# Bio_v4_LCD0_2.net
KiCad netlist of a schematic drawn in EAGLE
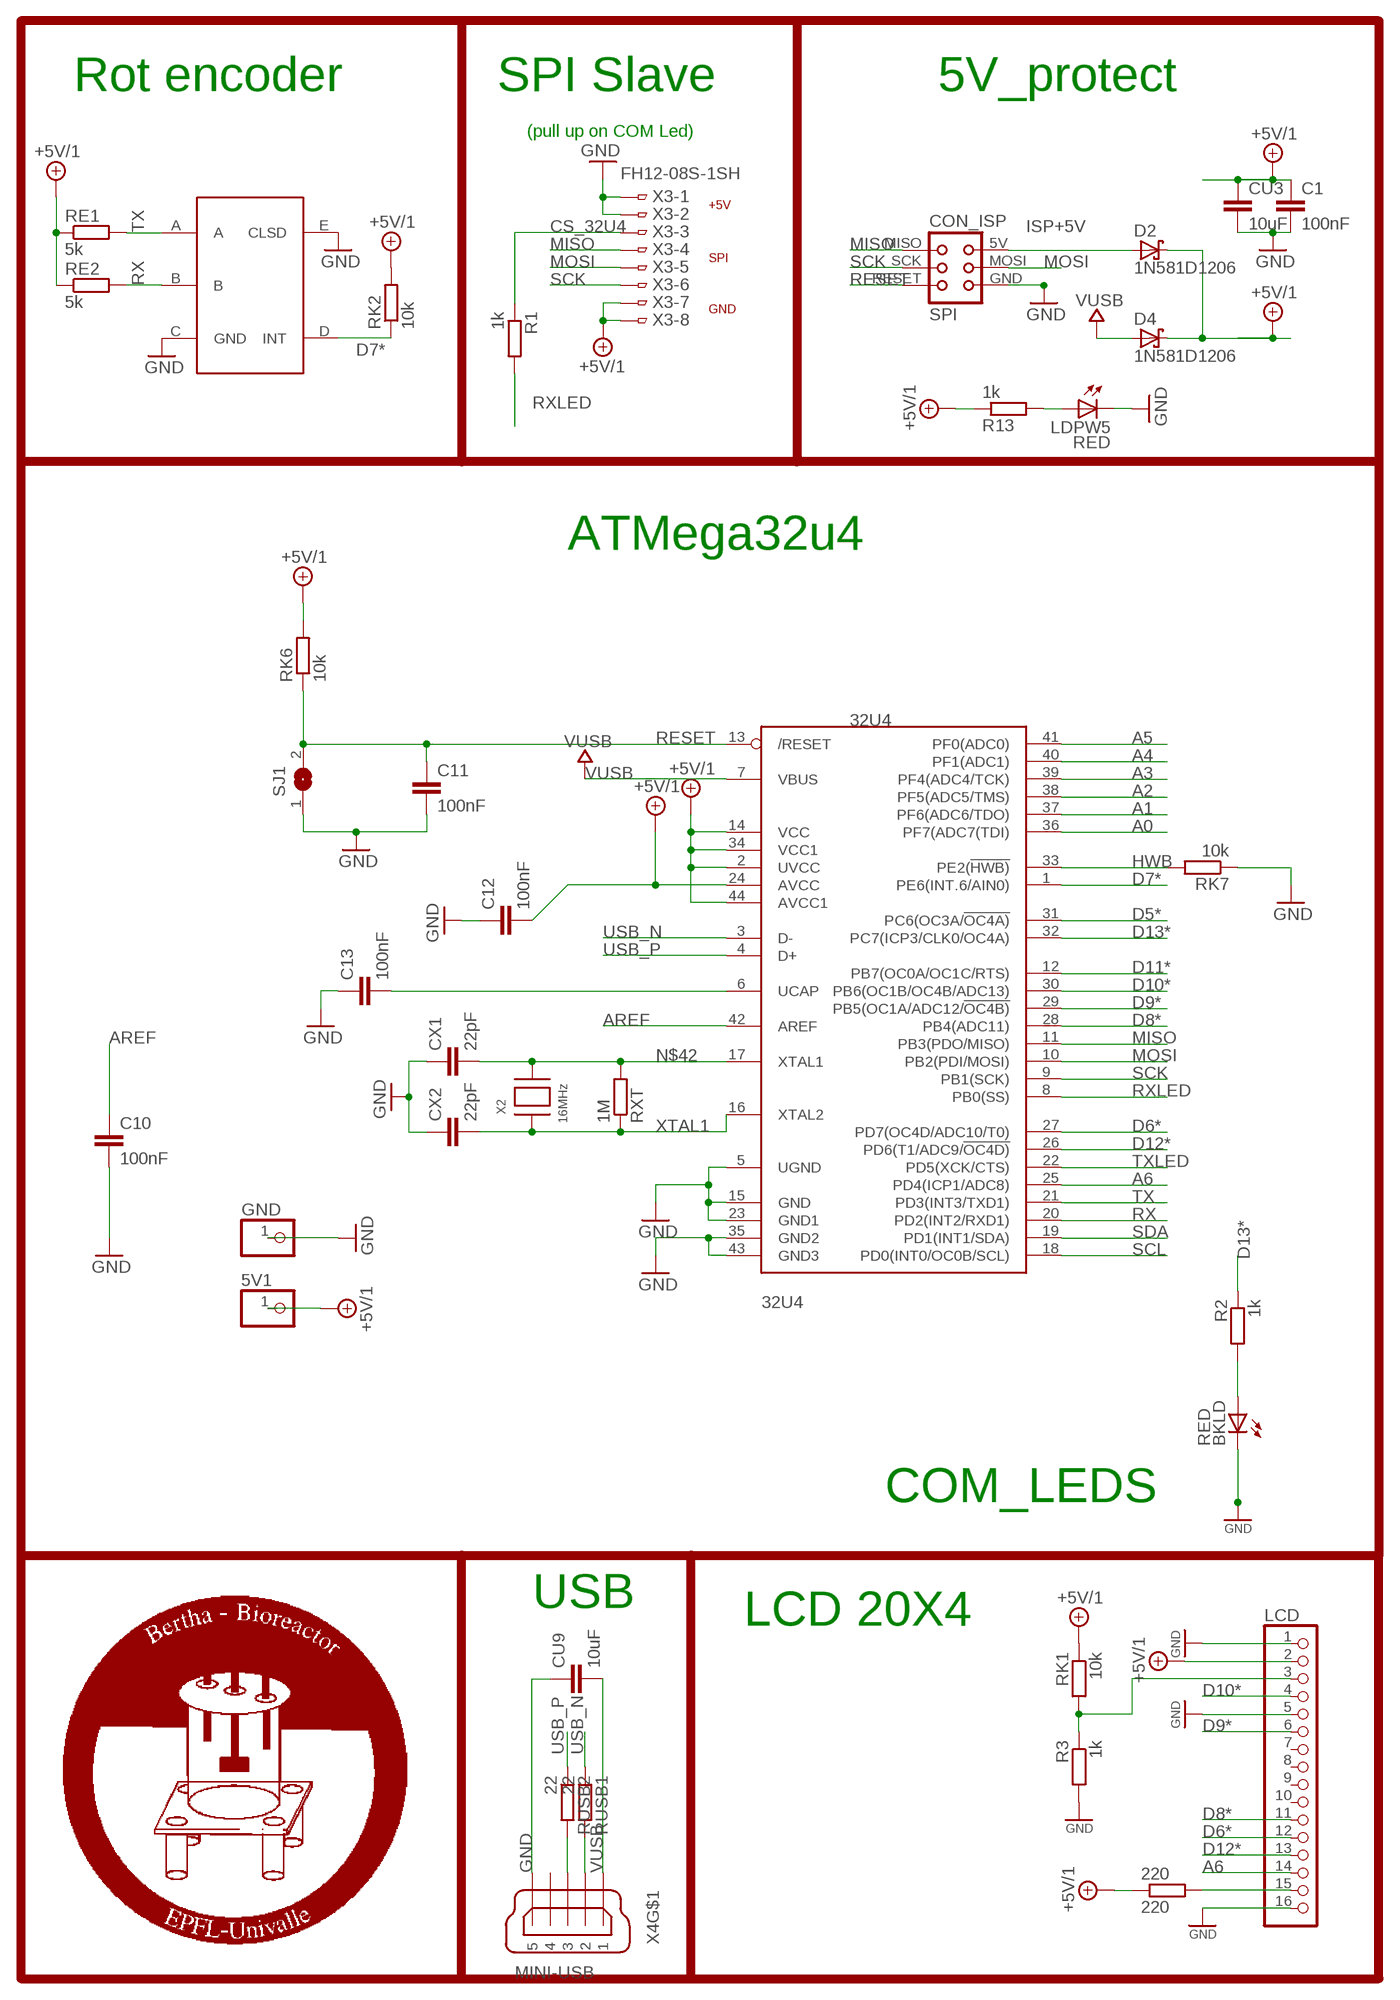
[diagram p0: schematic, sheet 1]

(export (version "E")
  (design (tool "Eeschema 10.0.6"))
  (components
    (comp (ref "5V1")
      (value "PINHD-1X1")
      (footprint "eagle-import:1X01")
      (libsource (lib "eagle-import") (part "PINHD-1X1"))
    )
    (comp (ref "32U4")
      (value "32U4")
      (footprint "eagle-import:TQFP44")
      (libsource (lib "eagle-import") (part "ATMEGA32U4-AU"))
    )
    (comp (ref "220")
      (value "220")
      (footprint "eagle-import:R0805")
      (libsource (lib "eagle-import") (part "R-EU_R0805"))
    )
    (comp (ref "BKLD")
      (value "RED")
      (footprint "eagle-import:CHIP-LED0805")
      (libsource (lib "eagle-import") (part "LEDCHIP-LED0805"))
    )
    (comp (ref "C1")
      (value "100nF")
      (footprint "eagle-import:C1206")
      (libsource (lib "eagle-import") (part "C-EUC1206"))
    )
    (comp (ref "C10")
      (value "100nF")
      (footprint "eagle-import:C1206")
      (libsource (lib "eagle-import") (part "C-EUC1206"))
    )
    (comp (ref "C11")
      (value "100nF")
      (footprint "eagle-import:C1206")
      (libsource (lib "eagle-import") (part "C-EUC1206"))
    )
    (comp (ref "C12")
      (value "100nF")
      (footprint "eagle-import:C1206")
      (libsource (lib "eagle-import") (part "C-EUC1206"))
    )
    (comp (ref "C13")
      (value "100nF")
      (footprint "eagle-import:C1206")
      (libsource (lib "eagle-import") (part "C-EUC1206"))
    )
    (comp (ref "CON_ISP")
      (value "SPI")
      (footprint "eagle-import:TC2030-MCP-NL")
      (libsource (lib "eagle-import") (part "TINYISPT"))
    )
    (comp (ref "CU3")
      (value "10uF")
      (footprint "eagle-import:C1206")
      (libsource (lib "eagle-import") (part "C-EUC1206"))
    )
    (comp (ref "CU9")
      (value "10uF")
      (footprint "eagle-import:C1206")
      (libsource (lib "eagle-import") (part "C-EUC1206"))
    )
    (comp (ref "CX1")
      (value "22pF")
      (footprint "eagle-import:C1206")
      (libsource (lib "eagle-import") (part "C-EUC1206"))
    )
    (comp (ref "CX2")
      (value "22pF")
      (footprint "eagle-import:C1206")
      (libsource (lib "eagle-import") (part "C-EUC1206"))
    )
    (comp (ref "D2")
      (value "1N581D1206")
      (footprint "eagle-import:LED-1206")
      (libsource (lib "eagle-import") (part "1N581D1206"))
    )
    (comp (ref "D4")
      (value "1N581D1206")
      (footprint "eagle-import:LED-1206")
      (libsource (lib "eagle-import") (part "1N581D1206"))
    )
    (comp (ref "GND")
      (value "PINHD-1X1")
      (footprint "eagle-import:1X01")
      (libsource (lib "eagle-import") (part "PINHD-1X1"))
    )
    (comp (ref "LCD")
      (value "LCD-HEADER")
      (footprint "eagle-import:1X16")
      (libsource (lib "eagle-import") (part "LCD-HEADER"))
    )
    (comp (ref "LDPW5")
      (value "RED")
      (footprint "eagle-import:CHIP-LED0805")
      (libsource (lib "eagle-import") (part "LEDCHIP-LED0805"))
    )
    (comp (ref "R1")
      (value "1k")
      (footprint "eagle-import:R0805")
      (libsource (lib "eagle-import") (part "R-EU_R0805"))
    )
    (comp (ref "R2")
      (value "1k")
      (footprint "eagle-import:R0805")
      (libsource (lib "eagle-import") (part "R-EU_R0805"))
    )
    (comp (ref "R3")
      (value "1k")
      (footprint "eagle-import:R0805")
      (libsource (lib "eagle-import") (part "R-EU_R0805"))
    )
    (comp (ref "R13")
      (value "1k")
      (footprint "eagle-import:R0805")
      (libsource (lib "eagle-import") (part "resistor_R-EU_R0805"))
    )
    (comp (ref "RE1")
      (value "5k")
      (footprint "eagle-import:R0805")
      (libsource (lib "eagle-import") (part "R-EU_R0805"))
    )
    (comp (ref "RE2")
      (value "5k")
      (footprint "eagle-import:R0805")
      (libsource (lib "eagle-import") (part "R-EU_R0805"))
    )
    (comp (ref "RK1")
      (value "10k")
      (footprint "eagle-import:R0805")
      (libsource (lib "eagle-import") (part "R-EU_R0805"))
    )
    (comp (ref "RK2")
      (value "10k")
      (footprint "eagle-import:M0805")
      (libsource (lib "eagle-import") (part "resistor_R-EU_M0805"))
    )
    (comp (ref "RK6")
      (value "10k")
      (footprint "eagle-import:M0805")
      (libsource (lib "eagle-import") (part "resistor_R-EU_M0805"))
    )
    (comp (ref "RK7")
      (value "10k")
      (footprint "eagle-import:M0805")
      (libsource (lib "eagle-import") (part "resistor_R-EU_M0805"))
    )
    (comp (ref "RUSB1")
      (value "22")
      (footprint "eagle-import:M1206")
      (libsource (lib "eagle-import") (part "resistor_R-EU_M1206"))
    )
    (comp (ref "RUSB2")
      (value "22")
      (footprint "eagle-import:M1206")
      (libsource (lib "eagle-import") (part "resistor_R-EU_M1206"))
    )
    (comp (ref "RXT")
      (value "1M")
      (footprint "eagle-import:R0805")
      (libsource (lib "eagle-import") (part "R-EU_R0805"))
    )
    (comp (ref "SJ1") (value "SJ") (footprint "eagle-import:SJ") (libsource (lib "eagle-import") (part "SJ")))
    (comp (ref "U$1")
      (value "EC11E")
      (footprint "eagle-import:EC11E")
      (libsource (lib "eagle-import") (part "EC11E"))
    )
    (comp (ref "X2")
      (value "16MHz")
      (footprint "eagle-import:NX6035")
      (libsource (lib "eagle-import") (part "XTALNX6035"))
    )
    (comp (ref "X3")
      (value "FH12-08S-1SH")
      (footprint "eagle-import:FH12-08S-1SH")
      (libsource (lib "eagle-import") (part "FH12-08S-1SH"))
    )
    (comp (ref "X4")
      (value "MINI-USB")
      (footprint "eagle-import:32005-201")
      (libsource (lib "eagle-import") (part "MINI-USB-SCHIELD-32005-201"))
    )
  )
  (nets
    (net (code "1") (name "+5V{slash}1") (class "Default")
      (node (ref "220") (pin "1") (pinfunction "1_1") (pintype "passive"))
      (node (ref "32U4") (pin "14") (pinfunction "VCC_14") (pintype "bidirectional"))
      (node (ref "32U4") (pin "2") (pinfunction "UVCC_2") (pintype "bidirectional"))
      (node (ref "32U4") (pin "24") (pinfunction "AVCC_24") (pintype "bidirectional"))
      (node (ref "32U4") (pin "34") (pinfunction "VCC1_34") (pintype "bidirectional"))
      (node (ref "32U4") (pin "44") (pinfunction "AVCC1_44") (pintype "bidirectional"))
      (node (ref "5V1") (pin "1") (pinfunction "1_1") (pintype "passive"))
      (node (ref "C1") (pin "1") (pinfunction "1_1") (pintype "passive"))
      (node (ref "C12") (pin "2") (pinfunction "2_2") (pintype "passive"))
      (node (ref "CU3") (pin "1") (pinfunction "1_1") (pintype "passive"))
      (node (ref "D2") (pin "C") (pinfunction "C_C") (pintype "passive"))
      (node (ref "D4") (pin "C") (pinfunction "C_C") (pintype "passive"))
      (node (ref "LCD") (pin "2") (pinfunction "2_2") (pintype "passive"))
      (node (ref "R13") (pin "1") (pinfunction "1_1") (pintype "passive"))
      (node (ref "RE1") (pin "1") (pinfunction "1_1") (pintype "passive"))
      (node (ref "RE2") (pin "1") (pinfunction "1_1") (pintype "passive"))
      (node (ref "RK1") (pin "1") (pinfunction "1_1") (pintype "passive"))
      (node (ref "RK2") (pin "2") (pinfunction "2_2") (pintype "passive"))
      (node (ref "RK6") (pin "2") (pinfunction "2_2") (pintype "passive"))
      (node (ref "X3") (pin "7") (pinfunction "1_7") (pintype "passive"))
      (node (ref "X3") (pin "8") (pinfunction "1_8") (pintype "passive"))
    )
    (net (code "2") (name "/A0") (class "Default")
      (node (ref "32U4") (pin "36") (pinfunction "PF7(ADC7(TDI)_36") (pintype "bidirectional"))
    )
    (net (code "3") (name "/A1") (class "Default")
      (node (ref "32U4") (pin "37") (pinfunction "PF6(ADC6/TDO)_37") (pintype "bidirectional"))
    )
    (net (code "4") (name "/A2") (class "Default")
      (node (ref "32U4") (pin "38") (pinfunction "PF5(ADC5/TMS)_38") (pintype "bidirectional"))
    )
    (net (code "5") (name "/A3") (class "Default")
      (node (ref "32U4") (pin "39") (pinfunction "PF4(ADC4/TCK)_39") (pintype "bidirectional"))
    )
    (net (code "6") (name "/A4") (class "Default")
      (node (ref "32U4") (pin "40") (pinfunction "PF1(ADC1)_40") (pintype "bidirectional"))
    )
    (net (code "7") (name "/A5") (class "Default")
      (node (ref "32U4") (pin "41") (pinfunction "PF0(ADC0)_41") (pintype "bidirectional"))
    )
    (net (code "8") (name "/A6") (class "Default")
      (node (ref "32U4") (pin "25") (pinfunction "PD4(ICP1/ADC8)_25") (pintype "bidirectional"))
      (node (ref "LCD") (pin "14") (pinfunction "14_14") (pintype "passive"))
    )
    (net (code "9") (name "/AREF") (class "Default")
      (node (ref "32U4") (pin "42") (pinfunction "AREF_42") (pintype "bidirectional"))
      (node (ref "C10") (pin "1") (pinfunction "1_1") (pintype "passive"))
    )
    (net (code "10") (name "/CS_32U4") (class "Default")
      (node (ref "R1") (pin "1") (pinfunction "1_1") (pintype "passive"))
      (node (ref "X3") (pin "3") (pinfunction "1_3") (pintype "passive"))
    )
    (net (code "11") (name "/D5*") (class "Default")
      (node (ref "32U4") (pin "31") (pinfunction "PC6(OC3A/~{OC4A})_31") (pintype "bidirectional"))
    )
    (net (code "12") (name "/D6*") (class "Default")
      (node (ref "32U4") (pin "27") (pinfunction "PD7(OC4D/ADC10/T0)_27") (pintype "bidirectional"))
      (node (ref "LCD") (pin "12") (pinfunction "12_12") (pintype "passive"))
    )
    (net (code "13") (name "/D7*") (class "Default")
      (node (ref "32U4") (pin "1") (pinfunction "PE6(INT.6/AIN0)_1") (pintype "bidirectional"))
      (node (ref "RK2") (pin "1") (pinfunction "1_1") (pintype "passive"))
      (node (ref "U$1") (pin "D") (pinfunction "INT_D") (pintype "bidirectional"))
    )
    (net (code "14") (name "/D8*") (class "Default")
      (node (ref "32U4") (pin "28") (pinfunction "PB4(ADC11)_28") (pintype "bidirectional"))
      (node (ref "LCD") (pin "11") (pinfunction "11_11") (pintype "passive"))
    )
    (net (code "15") (name "/D9*") (class "Default")
      (node (ref "32U4") (pin "29") (pinfunction "PB5(OC1A/ADC12/~{OC4B})_29") (pintype "bidirectional"))
      (node (ref "LCD") (pin "6") (pinfunction "6_6") (pintype "passive"))
    )
    (net (code "16") (name "/D10*") (class "Default")
      (node (ref "32U4") (pin "30") (pinfunction "PB6(OC1B/OC4B/ADC13)_30") (pintype "bidirectional"))
      (node (ref "LCD") (pin "4") (pinfunction "4_4") (pintype "passive"))
    )
    (net (code "17") (name "/D11*") (class "Default")
      (node (ref "32U4") (pin "12") (pinfunction "PB7(OC0A/OC1C/RTS)_12") (pintype "bidirectional"))
    )
    (net (code "18") (name "/D12*") (class "Default")
      (node (ref "32U4") (pin "26") (pinfunction "PD6(T1/ADC9/~{OC4D})_26") (pintype "bidirectional"))
      (node (ref "LCD") (pin "13") (pinfunction "13_13") (pintype "passive"))
    )
    (net (code "19") (name "/D13*") (class "Default")
      (node (ref "32U4") (pin "32") (pinfunction "PC7(ICP3/CLK0/OC4A)_32") (pintype "bidirectional"))
      (node (ref "R2") (pin "1") (pinfunction "1_1") (pintype "passive"))
    )
    (net (code "20") (name "/HWB") (class "Default")
      (node (ref "32U4") (pin "33") (pinfunction "PE2(~{HWB})_33") (pintype "bidirectional"))
      (node (ref "RK7") (pin "2") (pinfunction "2_2") (pintype "passive"))
    )
    (net (code "21") (name "/ISP+5V") (class "Default")
      (node (ref "CON_ISP") (pin "5V") (pinfunction "VCC_5V") (pintype "passive"))
      (node (ref "D2") (pin "A") (pinfunction "A_A") (pintype "passive"))
    )
    (net (code "22") (name "/MISO") (class "Default")
      (node (ref "32U4") (pin "11") (pinfunction "PB3(PDO/MISO)_11") (pintype "bidirectional"))
      (node (ref "CON_ISP") (pin "MISO") (pinfunction "MISO_MISO") (pintype "passive"))
      (node (ref "X3") (pin "4") (pinfunction "1_4") (pintype "passive"))
    )
    (net (code "23") (name "/MOSI") (class "Default")
      (node (ref "32U4") (pin "10") (pinfunction "PB2(PDI/MOSI)_10") (pintype "bidirectional"))
      (node (ref "CON_ISP") (pin "MOSI") (pinfunction "MOSI_MOSI") (pintype "passive"))
      (node (ref "X3") (pin "5") (pinfunction "1_5") (pintype "passive"))
    )
    (net (code "24") (name "/N$42") (class "Default")
      (node (ref "32U4") (pin "17") (pinfunction "XTAL1_17") (pintype "bidirectional"))
      (node (ref "CX1") (pin "2") (pinfunction "2_2") (pintype "passive"))
      (node (ref "RXT") (pin "2") (pinfunction "2_2") (pintype "passive"))
      (node (ref "X2") (pin "P$2") (pinfunction "P$2_P$2") (pintype "bidirectional"))
    )
    (net (code "25") (name "/RESET") (class "Default")
      (node (ref "32U4") (pin "13") (pinfunction "/RESET_13") (pintype "bidirectional"))
      (node (ref "C11") (pin "1") (pinfunction "1_1") (pintype "passive"))
      (node (ref "CON_ISP") (pin "RESET") (pinfunction "RESET_RESET") (pintype "passive"))
      (node (ref "RK6") (pin "1") (pinfunction "1_1") (pintype "passive"))
      (node (ref "SJ1") (pin "2") (pinfunction "2_2") (pintype "passive"))
    )
    (net (code "26") (name "/RX") (class "Default")
      (node (ref "32U4") (pin "20") (pinfunction "PD2(INT2/RXD1)_20") (pintype "bidirectional"))
      (node (ref "RE2") (pin "2") (pinfunction "2_2") (pintype "passive"))
      (node (ref "U$1") (pin "B") (pinfunction "B_B") (pintype "bidirectional"))
    )
    (net (code "27") (name "/RXLED") (class "Default")
      (node (ref "32U4") (pin "8") (pinfunction "PB0(SS)_8") (pintype "bidirectional"))
      (node (ref "R1") (pin "2") (pinfunction "2_2") (pintype "passive"))
    )
    (net (code "28") (name "/SCK") (class "Default")
      (node (ref "32U4") (pin "9") (pinfunction "PB1(SCK)_9") (pintype "bidirectional"))
      (node (ref "CON_ISP") (pin "SCK") (pinfunction "SCK_SCK") (pintype "passive"))
      (node (ref "X3") (pin "6") (pinfunction "1_6") (pintype "passive"))
    )
    (net (code "29") (name "/SCL") (class "Default")
      (node (ref "32U4") (pin "18") (pinfunction "PD0(INT0/OC0B/SCL)_18") (pintype "bidirectional"))
    )
    (net (code "30") (name "/SDA") (class "Default")
      (node (ref "32U4") (pin "19") (pinfunction "PD1(INT1/SDA)_19") (pintype "bidirectional"))
    )
    (net (code "31") (name "/TX") (class "Default")
      (node (ref "32U4") (pin "21") (pinfunction "PD3(INT3/TXD1)_21") (pintype "bidirectional"))
      (node (ref "RE1") (pin "2") (pinfunction "2_2") (pintype "passive"))
      (node (ref "U$1") (pin "A") (pinfunction "A_A") (pintype "bidirectional"))
    )
    (net (code "32") (name "/TXLED") (class "Default")
      (node (ref "32U4") (pin "22") (pinfunction "PD5(XCK/CTS)_22") (pintype "bidirectional"))
    )
    (net (code "33") (name "/USB_N") (class "Default")
      (node (ref "32U4") (pin "3") (pinfunction "D-_3") (pintype "bidirectional"))
      (node (ref "RUSB1") (pin "1") (pinfunction "1_1") (pintype "passive"))
    )
    (net (code "34") (name "/USB_P") (class "Default")
      (node (ref "32U4") (pin "4") (pinfunction "D+_4") (pintype "bidirectional"))
      (node (ref "RUSB2") (pin "1") (pinfunction "1_1") (pintype "passive"))
    )
    (net (code "35") (name "/XTAL1") (class "Default")
      (node (ref "32U4") (pin "16") (pinfunction "XTAL2_16") (pintype "bidirectional"))
      (node (ref "CX2") (pin "2") (pinfunction "2_2") (pintype "passive"))
      (node (ref "RXT") (pin "1") (pinfunction "1_1") (pintype "passive"))
      (node (ref "X2") (pin "P$1") (pinfunction "P$1_P$1") (pintype "bidirectional"))
    )
    (net (code "36") (name "GND") (class "Default")
      (node (ref "32U4") (pin "15") (pinfunction "GND_15") (pintype "bidirectional"))
      (node (ref "32U4") (pin "23") (pinfunction "GND1_23") (pintype "bidirectional"))
      (node (ref "32U4") (pin "35") (pinfunction "GND2_35") (pintype "bidirectional"))
      (node (ref "32U4") (pin "43") (pinfunction "GND3_43") (pintype "bidirectional"))
      (node (ref "32U4") (pin "5") (pinfunction "UGND_5") (pintype "bidirectional"))
      (node (ref "BKLD") (pin "C") (pinfunction "C_C") (pintype "passive"))
      (node (ref "C1") (pin "2") (pinfunction "2_2") (pintype "passive"))
      (node (ref "C10") (pin "2") (pinfunction "2_2") (pintype "passive"))
      (node (ref "C11") (pin "2") (pinfunction "2_2") (pintype "passive"))
      (node (ref "C12") (pin "1") (pinfunction "1_1") (pintype "passive"))
      (node (ref "C13") (pin "1") (pinfunction "1_1") (pintype "passive"))
      (node (ref "CON_ISP") (pin "GND") (pinfunction "GND_GND") (pintype "passive"))
      (node (ref "CU3") (pin "2") (pinfunction "2_2") (pintype "passive"))
      (node (ref "CU9") (pin "1") (pinfunction "1_1") (pintype "passive"))
      (node (ref "CX1") (pin "1") (pinfunction "1_1") (pintype "passive"))
      (node (ref "CX2") (pin "1") (pinfunction "1_1") (pintype "passive"))
      (node (ref "GND") (pin "1") (pinfunction "1_1") (pintype "passive"))
      (node (ref "LCD") (pin "1") (pinfunction "1_1") (pintype "passive"))
      (node (ref "LCD") (pin "16") (pinfunction "16_16") (pintype "passive"))
      (node (ref "LCD") (pin "5") (pinfunction "5_5") (pintype "passive"))
      (node (ref "LDPW5") (pin "C") (pinfunction "C_C") (pintype "passive"))
      (node (ref "R3") (pin "2") (pinfunction "2_2") (pintype "passive"))
      (node (ref "RK7") (pin "1") (pinfunction "1_1") (pintype "passive"))
      (node (ref "SJ1") (pin "1") (pinfunction "1_1") (pintype "passive"))
      (node (ref "U$1") (pin "C") (pinfunction "GND_C") (pintype "bidirectional"))
      (node (ref "U$1") (pin "E") (pinfunction "CLSD_E") (pintype "bidirectional"))
      (node (ref "X3") (pin "1") (pinfunction "1_1") (pintype "passive"))
      (node (ref "X3") (pin "2") (pinfunction "1_2") (pintype "passive"))
      (node (ref "X4") (pin "5") (pinfunction "5_5") (pintype "passive"))
    )
    (net (code "37") (name "Net-(32U4-UCAP)") (class "Default")
      (node (ref "32U4") (pin "6") (pinfunction "UCAP_6") (pintype "bidirectional"))
      (node (ref "C13") (pin "2") (pinfunction "2_2") (pintype "passive"))
    )
    (net (code "38") (name "Net-(220-Pad2)") (class "Default")
      (node (ref "220") (pin "2") (pinfunction "2_2") (pintype "passive"))
      (node (ref "LCD") (pin "15") (pinfunction "15_15") (pintype "passive"))
    )
    (net (code "39") (name "Net-(BKLD-PadA)") (class "Default")
      (node (ref "BKLD") (pin "A") (pinfunction "A_A") (pintype "passive"))
      (node (ref "R2") (pin "2") (pinfunction "2_2") (pintype "passive"))
    )
    (net (code "40") (name "Net-(LCD-Pad3)") (class "Default")
      (node (ref "LCD") (pin "3") (pinfunction "3_3") (pintype "passive"))
      (node (ref "R3") (pin "1") (pinfunction "1_1") (pintype "passive"))
      (node (ref "RK1") (pin "2") (pinfunction "2_2") (pintype "passive"))
    )
    (net (code "41") (name "Net-(LDPW5-PadA)") (class "Default")
      (node (ref "LDPW5") (pin "A") (pinfunction "A_A") (pintype "passive"))
      (node (ref "R13") (pin "2") (pinfunction "2_2") (pintype "passive"))
    )
    (net (code "42") (name "Net-(RUSB1-Pad2)") (class "Default")
      (node (ref "RUSB1") (pin "2") (pinfunction "2_2") (pintype "passive"))
      (node (ref "X4") (pin "2") (pinfunction "2_2") (pintype "passive"))
    )
    (net (code "43") (name "Net-(RUSB2-Pad2)") (class "Default")
      (node (ref "RUSB2") (pin "2") (pinfunction "2_2") (pintype "passive"))
      (node (ref "X4") (pin "3") (pinfunction "3_3") (pintype "passive"))
    )
    (net (code "44") (name "VUSB") (class "Default")
      (node (ref "32U4") (pin "7") (pinfunction "VBUS_7") (pintype "bidirectional"))
      (node (ref "CU9") (pin "2") (pinfunction "2_2") (pintype "passive"))
      (node (ref "D4") (pin "A") (pinfunction "A_A") (pintype "passive"))
      (node (ref "X4") (pin "1") (pinfunction "1_1") (pintype "passive"))
    )
    (net (code "45") (name "unconnected-(LCD-Pad7)") (class "Default")
      (node (ref "LCD") (pin "7") (pinfunction "7_7") (pintype "passive"))
    )
    (net (code "46") (name "unconnected-(LCD-Pad8)") (class "Default")
      (node (ref "LCD") (pin "8") (pinfunction "8_8") (pintype "passive"))
    )
    (net (code "47") (name "unconnected-(LCD-Pad9)") (class "Default")
      (node (ref "LCD") (pin "9") (pinfunction "9_9") (pintype "passive"))
    )
    (net (code "48") (name "unconnected-(LCD-Pad10)") (class "Default")
      (node (ref "LCD") (pin "10") (pinfunction "10_10") (pintype "passive"))
    )
    (net (code "49") (name "unconnected-(X4-Pad4)") (class "Default")
      (node (ref "X4") (pin "4") (pinfunction "4_4") (pintype "passive"))
    )
  )
)
